# icsp_adapter.net
KiCad netlist of a schematic drawn in EAGLE
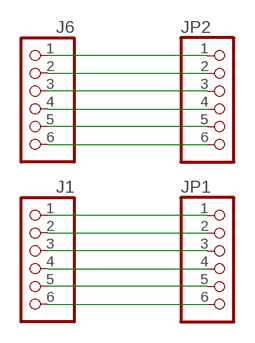
[diagram p0: schematic, sheet 1]

(export (version "E")
  (design (tool "Eeschema 10.0.6"))
  (components
    (comp (ref "J1")
      (value "PH1X650MIL")
      (footprint "eagle-import:PH1X6_50MIL")
      (libsource (lib "eagle-import") (part "PH1X650MIL"))
    )
    (comp (ref "J6")
      (value "PH1X650MIL")
      (footprint "eagle-import:PH1X6_50MIL")
      (libsource (lib "eagle-import") (part "PH1X650MIL"))
    )
    (comp (ref "JP1")
      (value "PINHD-1X6")
      (footprint "eagle-import:1X06")
      (libsource (lib "eagle-import") (part "PINHD-1X6"))
    )
    (comp (ref "JP2")
      (value "PINHD-1X6")
      (footprint "eagle-import:1X06")
      (libsource (lib "eagle-import") (part "PINHD-1X6"))
    )
  )
  (nets
    (net (code "1") (name "Net-(J1-Pad1)") (class "Default")
      (node (ref "J1") (pin "1") (pinfunction "1_1") (pintype "passive"))
      (node (ref "JP1") (pin "1") (pinfunction "1_1") (pintype "passive"))
    )
    (net (code "2") (name "Net-(J1-Pad2)") (class "Default")
      (node (ref "J1") (pin "2") (pinfunction "2_2") (pintype "passive"))
      (node (ref "JP1") (pin "2") (pinfunction "2_2") (pintype "passive"))
    )
    (net (code "3") (name "Net-(J1-Pad3)") (class "Default")
      (node (ref "J1") (pin "3") (pinfunction "3_3") (pintype "passive"))
      (node (ref "JP1") (pin "3") (pinfunction "3_3") (pintype "passive"))
    )
    (net (code "4") (name "Net-(J1-Pad4)") (class "Default")
      (node (ref "J1") (pin "4") (pinfunction "4_4") (pintype "passive"))
      (node (ref "JP1") (pin "4") (pinfunction "4_4") (pintype "passive"))
    )
    (net (code "5") (name "Net-(J1-Pad5)") (class "Default")
      (node (ref "J1") (pin "5") (pinfunction "5_5") (pintype "passive"))
      (node (ref "JP1") (pin "5") (pinfunction "5_5") (pintype "passive"))
    )
    (net (code "6") (name "Net-(J1-Pad6)") (class "Default")
      (node (ref "J1") (pin "6") (pinfunction "6_6") (pintype "passive"))
      (node (ref "JP1") (pin "6") (pinfunction "6_6") (pintype "passive"))
    )
    (net (code "7") (name "Net-(J6-Pad1)") (class "Default")
      (node (ref "J6") (pin "1") (pinfunction "1_1") (pintype "passive"))
      (node (ref "JP2") (pin "1") (pinfunction "1_1") (pintype "passive"))
    )
    (net (code "8") (name "Net-(J6-Pad2)") (class "Default")
      (node (ref "J6") (pin "2") (pinfunction "2_2") (pintype "passive"))
      (node (ref "JP2") (pin "2") (pinfunction "2_2") (pintype "passive"))
    )
    (net (code "9") (name "Net-(J6-Pad3)") (class "Default")
      (node (ref "J6") (pin "3") (pinfunction "3_3") (pintype "passive"))
      (node (ref "JP2") (pin "3") (pinfunction "3_3") (pintype "passive"))
    )
    (net (code "10") (name "Net-(J6-Pad4)") (class "Default")
      (node (ref "J6") (pin "4") (pinfunction "4_4") (pintype "passive"))
      (node (ref "JP2") (pin "4") (pinfunction "4_4") (pintype "passive"))
    )
    (net (code "11") (name "Net-(J6-Pad5)") (class "Default")
      (node (ref "J6") (pin "5") (pinfunction "5_5") (pintype "passive"))
      (node (ref "JP2") (pin "5") (pinfunction "5_5") (pintype "passive"))
    )
    (net (code "12") (name "Net-(J6-Pad6)") (class "Default")
      (node (ref "J6") (pin "6") (pinfunction "6_6") (pintype "passive"))
      (node (ref "JP2") (pin "6") (pinfunction "6_6") (pintype "passive"))
    )
  )
)
